# indicator_leds.net
KiCad netlist of a schematic drawn in Altium Designer
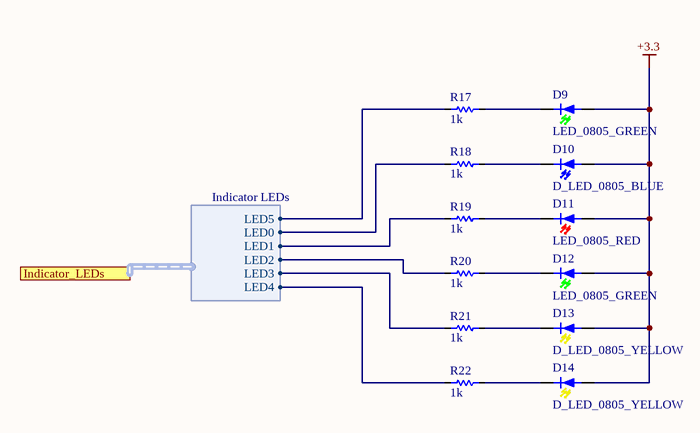
[diagram p0: indicator_leds.SchDoc]

(export (version "E")
  (design (tool "Eeschema 10.0.6"))
  (components
    (comp (ref "D9")
      (value "LED_0805_GREEN")
      (footprint "0805_LED_Green")
      (description "LED CHIPLED 570NM GREEN 0805 SMD")
      (fields
        (field (name "MANUFACTURER") "Osram Opto Semiconductors Inc")
        (field (name "SVP CREATOR") "Nate Bolyard")
      )
      (libsource (lib "") (part "Symbol_1"))
    )
    (comp (ref "D10")
      (value "D_LED_0805_BLUE")
      (footprint "0805_LED_Blue")
      (description "LED 2X1.2MM 470NM BL WTR CLR SMD")
      (fields (field (name "MANUFACTURER") "Kingbright") (field (name "SVP CREATOR") "Jonathan Nutzmann"))
      (libsource (lib "") (part "Symbol_1"))
    )
    (comp (ref "D11")
      (value "LED_0805_RED")
      (footprint "0805_LED_Red")
      (description "LED CHIPLED 645NM RED DIFF 0805")
      (fields
        (field (name "MANUFACTURER") "OSRAM Opto Semiconductors Inc")
        (field (name "SVP CREATOR") "Jonathan Nutzmann")
      )
      (libsource (lib "") (part "Symbol_1"))
    )
    (comp (ref "D12")
      (value "LED_0805_GREEN")
      (footprint "0805_LED_Green")
      (description "LED CHIPLED 570NM GREEN 0805 SMD")
      (fields
        (field (name "MANUFACTURER") "Osram Opto Semiconductors Inc")
        (field (name "SVP CREATOR") "Nate Bolyard")
      )
      (libsource (lib "") (part "Symbol_1"))
    )
    (comp (ref "D13")
      (value "D_LED_0805_YELLOW")
      (footprint "0805_LED_Yellow")
      (description "LED 595NM AMBER DIFF SMD 0805")
      (fields
        (field (name "MANUFACTURER") "Avago Technologies US Inc.")
        (field (name "SVP CREATOR") "Jonathan Nutzmann")
      )
      (libsource (lib "University of Minnesota - Solar Vehicle Project") (part "D_LED_0805_YELLOW"))
    )
    (comp (ref "D14")
      (value "D_LED_0805_YELLOW")
      (footprint "0805_LED_Yellow")
      (description "LED 595NM AMBER DIFF SMD 0805")
      (fields
        (field (name "MANUFACTURER") "Avago Technologies US Inc.")
        (field (name "SVP CREATOR") "Jonathan Nutzmann")
      )
      (libsource (lib "University of Minnesota - Solar Vehicle Project") (part "D_LED_0805_YELLOW"))
    )
    (comp (ref "R17")
      (value "1k")
      (footprint "0603_RESISTOR")
      (description "RES 1K OHM 1/16W 1% 0603 SMD")
      (fields (field (name "TOLERANCE") "1%") (field (name "POWER") "62.5mW"))
      (libsource (lib "University of Minnesota - Solar Vehicle Project") (part "Symbol"))
    )
    (comp (ref "R18")
      (value "1k")
      (footprint "0603_RESISTOR")
      (description "RES 1K OHM 1/16W 1% 0603 SMD")
      (fields (field (name "TOLERANCE") "1%") (field (name "POWER") "62.5mW"))
      (libsource (lib "University of Minnesota - Solar Vehicle Project") (part "Symbol"))
    )
    (comp (ref "R19")
      (value "1k")
      (footprint "0603_RESISTOR")
      (description "RES 1K OHM 1/16W 1% 0603 SMD")
      (fields (field (name "TOLERANCE") "1%") (field (name "POWER") "62.5mW"))
      (libsource (lib "University of Minnesota - Solar Vehicle Project") (part "Symbol"))
    )
    (comp (ref "R20")
      (value "1k")
      (footprint "0603_RESISTOR")
      (description "RES 1K OHM 1/16W 1% 0603 SMD")
      (fields (field (name "TOLERANCE") "1%") (field (name "POWER") "62.5mW"))
      (libsource (lib "University of Minnesota - Solar Vehicle Project") (part "Symbol"))
    )
    (comp (ref "R21")
      (value "1k")
      (footprint "0603_RESISTOR")
      (description "RES 1K OHM 1/16W 1% 0603 SMD")
      (fields (field (name "TOLERANCE") "1%") (field (name "POWER") "62.5mW"))
      (libsource (lib "University of Minnesota - Solar Vehicle Project") (part "Symbol"))
    )
    (comp (ref "R22")
      (value "1k")
      (footprint "0603_RESISTOR")
      (description "RES 1K OHM 1/16W 1% 0603 SMD")
      (fields (field (name "TOLERANCE") "1%") (field (name "POWER") "62.5mW"))
      (libsource (lib "University of Minnesota - Solar Vehicle Project") (part "Symbol"))
    )
  )
  (nets
    (net (code "3") (name "+3.3") (class "Default")
      (node (ref "D10") (pin "1") (pinfunction "Anode_1") (pintype "passive"))
      (node (ref "D11") (pin "1") (pinfunction "Anode_1") (pintype "passive"))
      (node (ref "D12") (pin "1") (pinfunction "Anode_1") (pintype "passive"))
      (node (ref "D13") (pin "1") (pinfunction "Anode_1") (pintype "passive"))
      (node (ref "D14") (pin "1") (pinfunction "Anode_1") (pintype "passive"))
      (node (ref "D9") (pin "1") (pinfunction "Anode_1") (pintype "passive"))
    )
    (net (code "4") (name "/LED0") (class "Default")
      (node (ref "R18") (pin "1") (pinfunction "1_1") (pintype "passive"))
    )
    (net (code "5") (name "/LED1") (class "Default")
      (node (ref "R19") (pin "1") (pinfunction "1_1") (pintype "passive"))
    )
    (net (code "6") (name "/LED2") (class "Default")
      (node (ref "R20") (pin "1") (pinfunction "1_1") (pintype "passive"))
    )
    (net (code "7") (name "/LED3") (class "Default")
      (node (ref "R21") (pin "1") (pinfunction "1_1") (pintype "passive"))
    )
    (net (code "8") (name "/LED4") (class "Default")
      (node (ref "R22") (pin "1") (pinfunction "1_1") (pintype "passive"))
    )
    (net (code "9") (name "/LED5") (class "Default")
      (node (ref "R17") (pin "1") (pinfunction "1_1") (pintype "passive"))
    )
    (net (code "11") (name "Net-(D9-Cathode)") (class "Default")
      (node (ref "D9") (pin "2") (pinfunction "Cathode_2") (pintype "passive"))
      (node (ref "R17") (pin "2") (pinfunction "2_2") (pintype "passive"))
    )
    (net (code "12") (name "Net-(D10-Cathode)") (class "Default")
      (node (ref "D10") (pin "2") (pinfunction "Cathode_2") (pintype "passive"))
      (node (ref "R18") (pin "2") (pinfunction "2_2") (pintype "passive"))
    )
    (net (code "13") (name "Net-(D11-Cathode)") (class "Default")
      (node (ref "D11") (pin "2") (pinfunction "Cathode_2") (pintype "passive"))
      (node (ref "R19") (pin "2") (pinfunction "2_2") (pintype "passive"))
    )
    (net (code "14") (name "Net-(D12-Cathode)") (class "Default")
      (node (ref "D12") (pin "2") (pinfunction "Cathode_2") (pintype "passive"))
      (node (ref "R20") (pin "2") (pinfunction "2_2") (pintype "passive"))
    )
    (net (code "15") (name "Net-(D13-Cathode)") (class "Default")
      (node (ref "D13") (pin "2") (pinfunction "Cathode_2") (pintype "passive"))
      (node (ref "R21") (pin "2") (pinfunction "2_2") (pintype "passive"))
    )
    (net (code "16") (name "Net-(D14-Cathode)") (class "Default")
      (node (ref "D14") (pin "2") (pinfunction "Cathode_2") (pintype "passive"))
      (node (ref "R22") (pin "2") (pinfunction "2_2") (pintype "passive"))
    )
  )
)
